# Zx81CompositeSMD.net
KiCad netlist of a schematic drawn in EAGLE
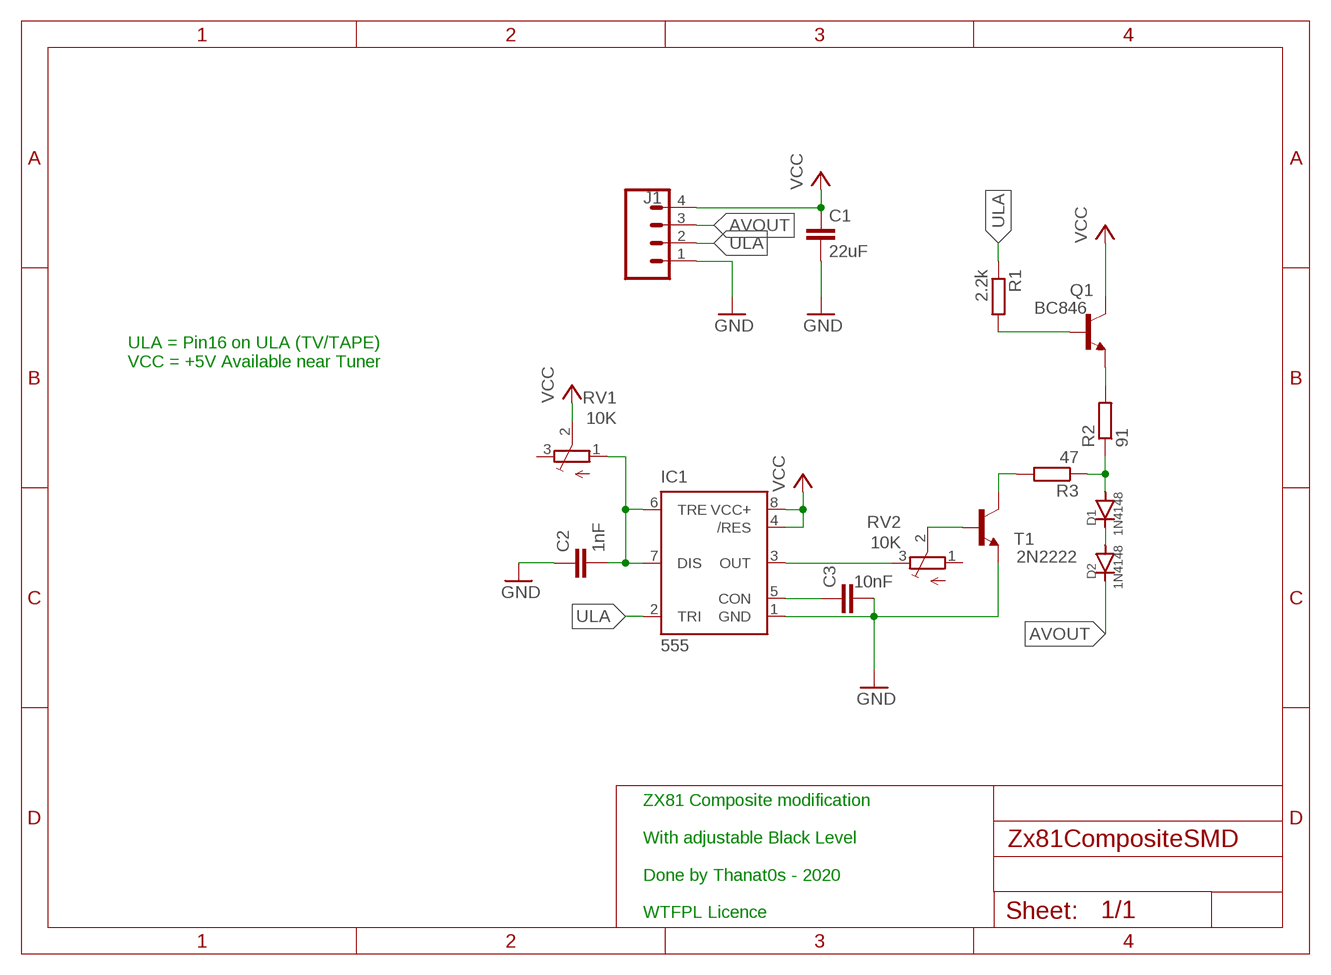
[diagram p0: schematic, sheet 1]

(export (version "E")
  (design (tool "Eeschema 10.0.6"))
  (components
    (comp (ref "C1")
      (value "22uF")
      (footprint "eagle-import:C1206K")
      (libsource (lib "eagle-import") (part "C-EUC1206K"))
    )
    (comp (ref "C2")
      (value "1nF")
      (footprint "eagle-import:C0603K")
      (libsource (lib "eagle-import") (part "C-EUC0603K"))
    )
    (comp (ref "C3")
      (value "10nF")
      (footprint "eagle-import:C0603K")
      (libsource (lib "eagle-import") (part "C-EUC0603K"))
    )
    (comp (ref "D1")
      (value "1N4148")
      (footprint "eagle-import:SOD-323")
      (fields
        (field (name "DIGIKEY_PART_NUMBER") "1N4148WSFSTR-ND")
        (field (name "MANUFACTURER") "Diodes Incorporated")
        (field (name "MPN") "1N4148WS")
        (field (name "CREATED_BY") "PCBLayout.com")
      )
      (libsource (lib "eagle-import") (part "1N4148WS"))
    )
    (comp (ref "D2")
      (value "1N4148")
      (footprint "eagle-import:SOD-323")
      (fields
        (field (name "DIGIKEY_PART_NUMBER") "1N4148WSFSTR-ND")
        (field (name "MANUFACTURER") "Diodes Incorporated")
        (field (name "MPN") "1N4148WS")
        (field (name "CREATED_BY") "PCBLayout.com")
      )
      (libsource (lib "eagle-import") (part "1N4148WS"))
    )
    (comp (ref "IC1")
      (value "555")
      (footprint "eagle-import:SO08")
      (libsource (lib "eagle-import") (part "555D"))
    )
    (comp (ref "J1")
      (value "CONN_04")
      (footprint "eagle-import:1X04")
      (libsource (lib "eagle-import") (part "CONN_04"))
    )
    (comp (ref "Q1")
      (value "BC846")
      (footprint "eagle-import:SOT23")
      (libsource (lib "eagle-import") (part "BC846"))
    )
    (comp (ref "R1")
      (value "2.2k")
      (footprint "eagle-import:R0603")
      (libsource (lib "eagle-import") (part "R-EU_R0603"))
    )
    (comp (ref "R2")
      (value "91")
      (footprint "eagle-import:R0603")
      (libsource (lib "eagle-import") (part "R-EU_R0603"))
    )
    (comp (ref "R3")
      (value "47")
      (footprint "eagle-import:R0603")
      (libsource (lib "eagle-import") (part "R-EU_R0603"))
    )
    (comp (ref "RV1")
      (value "10K")
      (footprint "eagle-import:SM-42_43A")
      (fields (field (name "SPICEPREFIX") "J"))
      (libsource (lib "eagle-import") (part "TRIM_EU-SM-42/43A"))
    )
    (comp (ref "RV2")
      (value "10K")
      (footprint "eagle-import:SM-42_43A")
      (fields (field (name "SPICEPREFIX") "J"))
      (libsource (lib "eagle-import") (part "TRIM_EU-SM-42/43A"))
    )
    (comp (ref "T1")
      (value "2N2222")
      (footprint "eagle-import:SOT23")
      (fields (field (name "SPICEPREFIX") "J"))
      (libsource (lib "eagle-import") (part "BC850"))
    )
  )
  (nets
    (net (code "1") (name "AVOUT") (class "Default")
      (node (ref "D2") (pin "C") (pinfunction "C_C") (pintype "passive"))
      (node (ref "J1") (pin "3") (pinfunction "3_3") (pintype "passive"))
    )
    (net (code "2") (name "GND") (class "Default")
      (node (ref "C1") (pin "2") (pinfunction "2_2") (pintype "passive"))
      (node (ref "C2") (pin "1") (pinfunction "1_1") (pintype "passive"))
      (node (ref "C3") (pin "2") (pinfunction "2_2") (pintype "passive"))
      (node (ref "IC1") (pin "1") (pinfunction "GND_1") (pintype "power_in"))
      (node (ref "J1") (pin "1") (pinfunction "1_1") (pintype "passive"))
      (node (ref "T1") (pin "2") (pinfunction "E_2") (pintype "passive"))
    )
    (net (code "3") (name "Net-(D1-PadA)") (class "Default")
      (node (ref "D1") (pin "A") (pinfunction "A_A") (pintype "passive"))
      (node (ref "R2") (pin "1") (pinfunction "1_1") (pintype "passive"))
      (node (ref "R3") (pin "1") (pinfunction "1_1") (pintype "passive"))
    )
    (net (code "4") (name "Net-(D1-PadC)") (class "Default")
      (node (ref "D1") (pin "C") (pinfunction "C_C") (pintype "passive"))
      (node (ref "D2") (pin "A") (pinfunction "A_A") (pintype "passive"))
    )
    (net (code "5") (name "Net-(IC1-CON)") (class "Default")
      (node (ref "C3") (pin "1") (pinfunction "1_1") (pintype "passive"))
      (node (ref "IC1") (pin "5") (pinfunction "CON_5") (pintype "input"))
    )
    (net (code "6") (name "Net-(IC1-DIS)") (class "Default")
      (node (ref "C2") (pin "2") (pinfunction "2_2") (pintype "passive"))
      (node (ref "IC1") (pin "6") (pinfunction "TRE_6") (pintype "input"))
      (node (ref "IC1") (pin "7") (pinfunction "DIS_7") (pintype "input"))
      (node (ref "RV1") (pin "1") (pinfunction "A_1") (pintype "passive"))
    )
    (net (code "7") (name "Net-(IC1-OUT)") (class "Default")
      (node (ref "IC1") (pin "3") (pinfunction "OUT_3") (pintype "output"))
      (node (ref "RV2") (pin "3") (pinfunction "E_3") (pintype "passive"))
    )
    (net (code "8") (name "Net-(Q1-B)") (class "Default")
      (node (ref "Q1") (pin "1") (pinfunction "B_1") (pintype "passive"))
      (node (ref "R1") (pin "2") (pinfunction "2_2") (pintype "passive"))
    )
    (net (code "9") (name "Net-(Q1-E)") (class "Default")
      (node (ref "Q1") (pin "2") (pinfunction "E_2") (pintype "passive"))
      (node (ref "R2") (pin "2") (pinfunction "2_2") (pintype "passive"))
    )
    (net (code "10") (name "Net-(RV2-S)") (class "Default")
      (node (ref "RV2") (pin "2") (pinfunction "S_2") (pintype "passive"))
      (node (ref "T1") (pin "1") (pinfunction "B_1") (pintype "passive"))
    )
    (net (code "11") (name "Net-(T1-C)") (class "Default")
      (node (ref "R3") (pin "2") (pinfunction "2_2") (pintype "passive"))
      (node (ref "T1") (pin "3") (pinfunction "C_3") (pintype "passive"))
    )
    (net (code "12") (name "ULA") (class "Default")
      (node (ref "IC1") (pin "2") (pinfunction "TRI_2") (pintype "input"))
      (node (ref "J1") (pin "2") (pinfunction "2_2") (pintype "passive"))
      (node (ref "R1") (pin "1") (pinfunction "1_1") (pintype "passive"))
    )
    (net (code "13") (name "VCC") (class "Default")
      (node (ref "C1") (pin "1") (pinfunction "1_1") (pintype "passive"))
      (node (ref "IC1") (pin "4") (pinfunction "/RES_4") (pintype "input"))
      (node (ref "IC1") (pin "8") (pinfunction "VCC+_8") (pintype "power_in"))
      (node (ref "J1") (pin "4") (pinfunction "4_4") (pintype "passive"))
      (node (ref "Q1") (pin "3") (pinfunction "C_3") (pintype "passive"))
      (node (ref "RV1") (pin "2") (pinfunction "S_2") (pintype "passive"))
    )
    (net (code "14") (name "unconnected-(RV1-E-Pad3)") (class "Default")
      (node (ref "RV1") (pin "3") (pinfunction "E_3") (pintype "passive"))
    )
    (net (code "15") (name "unconnected-(RV2-A-Pad1)") (class "Default")
      (node (ref "RV2") (pin "1") (pinfunction "A_1") (pintype "passive"))
    )
  )
)
